# Licznik_minut.net
KiCad netlist of a schematic drawn in Altium Designer
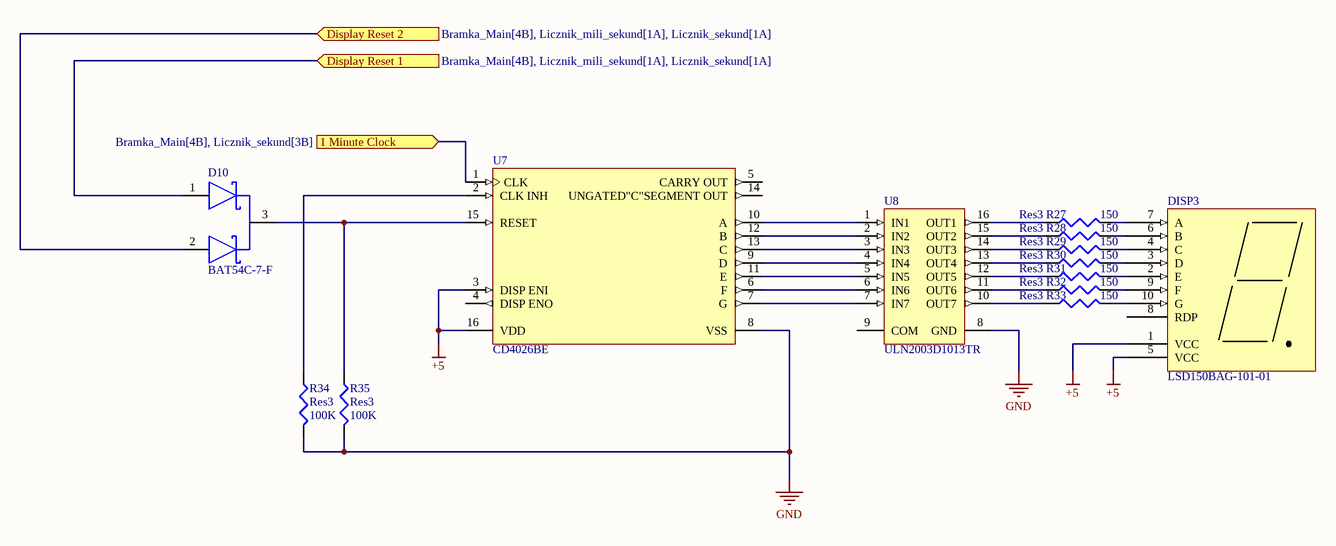
[diagram p0: Licznik_minut.SchDoc]

(export (version "E")
  (design (tool "Eeschema 10.0.6"))
  (components
    (comp (ref "D10")
      (value "BAT54C-7-F")
      (footprint "FP-SOT23-IPC_B")
      (description "DIODE ARRAY SCHOTTKY 30V SOT23-3")
      (libsource (lib "Altium Content Vault") (part "3eac2aa0c1ac86323ecc23460aa29c6"))
    )
    (comp (ref "DISP3")
      (value "LSD150BAG-101-01")
      (footprint "7 segment display")
      (description "7 segment display 1.5 inch")
      (libsource (lib "WUST") (part "LSD150BAG-101-01-Symbol-1"))
    )
    (comp (ref "R27")
      (value "Res3")
      (footprint "6-0805_M")
      (description "Resistor")
      (fields (field (name "ALTIUM_VALUE") "150") (field (name "PUBLISHER") "Altium Limited"))
      (libsource (lib "Miscellaneous Devices") (part "Res3"))
    )
    (comp (ref "R28")
      (value "Res3")
      (footprint "6-0805_M")
      (description "Resistor")
      (fields (field (name "ALTIUM_VALUE") "150") (field (name "PUBLISHER") "Altium Limited"))
      (libsource (lib "Miscellaneous Devices") (part "Res3"))
    )
    (comp (ref "R29")
      (value "Res3")
      (footprint "6-0805_M")
      (description "Resistor")
      (fields (field (name "ALTIUM_VALUE") "150") (field (name "PUBLISHER") "Altium Limited"))
      (libsource (lib "Miscellaneous Devices") (part "Res3"))
    )
    (comp (ref "R30")
      (value "Res3")
      (footprint "6-0805_M")
      (description "Resistor")
      (fields (field (name "ALTIUM_VALUE") "150") (field (name "PUBLISHER") "Altium Limited"))
      (libsource (lib "Miscellaneous Devices") (part "Res3"))
    )
    (comp (ref "R31")
      (value "Res3")
      (footprint "6-0805_M")
      (description "Resistor")
      (fields (field (name "ALTIUM_VALUE") "150") (field (name "PUBLISHER") "Altium Limited"))
      (libsource (lib "Miscellaneous Devices") (part "Res3"))
    )
    (comp (ref "R32")
      (value "Res3")
      (footprint "6-0805_M")
      (description "Resistor")
      (fields (field (name "ALTIUM_VALUE") "150") (field (name "PUBLISHER") "Altium Limited"))
      (libsource (lib "Miscellaneous Devices") (part "Res3"))
    )
    (comp (ref "R33")
      (value "Res3")
      (footprint "6-0805_M")
      (description "Resistor")
      (fields (field (name "ALTIUM_VALUE") "150") (field (name "PUBLISHER") "Altium Limited"))
      (libsource (lib "Miscellaneous Devices") (part "Res3"))
    )
    (comp (ref "R34")
      (value "Res3")
      (footprint "J1-0603")
      (description "Resistor")
      (fields (field (name "ALTIUM_VALUE") "100K") (field (name "PUBLISHER") "Altium Limited"))
      (libsource (lib "Miscellaneous Devices") (part "Res3"))
    )
    (comp (ref "R35")
      (value "Res3")
      (footprint "J1-0603")
      (description "Resistor")
      (fields (field (name "ALTIUM_VALUE") "100K") (field (name "PUBLISHER") "Altium Limited"))
      (libsource (lib "Miscellaneous Devices") (part "Res3"))
    )
    (comp (ref "U7")
      (value "CD4026BE")
      (footprint "N0016A")
      (fields
        (field (name "MANUFACTURER") "Texas Instruments")
        (field (name "GENERIC PART NUMBER") "CD4026B")
      )
      (libsource (lib "Altium Content Vault") (part "TI-CD4026B-16"))
    )
    (comp (ref "U8")
      (value "ULN2003D1013TR")
      (footprint "STM-SO-16_M")
      (fields (field (name "MANUFACTURER") "STMicroelectronics"))
      (libsource (lib "Altium Content Vault") (part "STM-ULN2003A-PDIP-16"))
    )
  )
  (nets
    (net (code "1") (name "+5") (class "Default")
      (node (ref "DISP3") (pin "1") (pinfunction "VCC_1") (pintype "power_in"))
      (node (ref "DISP3") (pin "5") (pinfunction "VCC_5") (pintype "power_in"))
      (node (ref "U7") (pin "16") (pinfunction "VDD_16") (pintype "power_in"))
      (node (ref "U7") (pin "3") (pinfunction "DISP_ENI_3") (pintype "input"))
    )
    (net (code "2") (name "/1 Minute Clock") (class "Default")
      (node (ref "U7") (pin "1") (pinfunction "CLK_1") (pintype "input"))
    )
    (net (code "3") (name "/Display Reset 1") (class "Default")
      (node (ref "D10") (pin "1") (pinfunction "1_ANODE_1") (pintype "passive"))
    )
    (net (code "4") (name "/Display Reset 2") (class "Default")
      (node (ref "D10") (pin "2") (pinfunction "2_ANODE_2") (pintype "passive"))
    )
    (net (code "5") (name "GND") (class "Default")
      (node (ref "R34") (pin "2") (pinfunction "2_2") (pintype "passive"))
      (node (ref "R35") (pin "2") (pinfunction "2_2") (pintype "passive"))
      (node (ref "U7") (pin "8") (pinfunction "VSS_8") (pintype "power_in"))
      (node (ref "U8") (pin "8") (pinfunction "GND_8") (pintype "power_in"))
    )
    (net (code "6") (name "Net-(D10-COMMON_CATHODE)") (class "Default")
      (node (ref "D10") (pin "3") (pinfunction "COMMON_CATHODE_3") (pintype "passive"))
      (node (ref "R35") (pin "1") (pinfunction "1_1") (pintype "passive"))
      (node (ref "U7") (pin "15") (pinfunction "RESET_15") (pintype "input"))
    )
    (net (code "7") (name "Net-(DISP3-A)") (class "Default")
      (node (ref "DISP3") (pin "7") (pinfunction "A_7") (pintype "input"))
      (node (ref "R27") (pin "2") (pinfunction "2_2") (pintype "passive"))
    )
    (net (code "8") (name "Net-(DISP3-B)") (class "Default")
      (node (ref "DISP3") (pin "6") (pinfunction "B_6") (pintype "input"))
      (node (ref "R28") (pin "2") (pinfunction "2_2") (pintype "passive"))
    )
    (net (code "9") (name "Net-(DISP3-C)") (class "Default")
      (node (ref "DISP3") (pin "4") (pinfunction "C_4") (pintype "input"))
      (node (ref "R29") (pin "2") (pinfunction "2_2") (pintype "passive"))
    )
    (net (code "10") (name "Net-(DISP3-D)") (class "Default")
      (node (ref "DISP3") (pin "3") (pinfunction "D_3") (pintype "input"))
      (node (ref "R30") (pin "2") (pinfunction "2_2") (pintype "passive"))
    )
    (net (code "11") (name "Net-(DISP3-E)") (class "Default")
      (node (ref "DISP3") (pin "2") (pinfunction "E_2") (pintype "input"))
      (node (ref "R31") (pin "2") (pinfunction "2_2") (pintype "passive"))
    )
    (net (code "12") (name "Net-(DISP3-F)") (class "Default")
      (node (ref "DISP3") (pin "9") (pinfunction "F_9") (pintype "input"))
      (node (ref "R32") (pin "2") (pinfunction "2_2") (pintype "passive"))
    )
    (net (code "13") (name "Net-(DISP3-G)") (class "Default")
      (node (ref "DISP3") (pin "10") (pinfunction "G_10") (pintype "input"))
      (node (ref "R33") (pin "2") (pinfunction "2_2") (pintype "passive"))
    )
    (net (code "14") (name "Net-(U7-A)") (class "Default")
      (node (ref "U7") (pin "10") (pinfunction "A_10") (pintype "output"))
      (node (ref "U8") (pin "1") (pinfunction "IN1_1") (pintype "input"))
    )
    (net (code "15") (name "Net-(U7-B)") (class "Default")
      (node (ref "U7") (pin "12") (pinfunction "B_12") (pintype "output"))
      (node (ref "U8") (pin "2") (pinfunction "IN2_2") (pintype "input"))
    )
    (net (code "16") (name "Net-(U7-C)") (class "Default")
      (node (ref "U7") (pin "13") (pinfunction "C_13") (pintype "output"))
      (node (ref "U8") (pin "3") (pinfunction "IN3_3") (pintype "input"))
    )
    (net (code "17") (name "Net-(U7-CLK_INH)") (class "Default")
      (node (ref "R34") (pin "1") (pinfunction "1_1") (pintype "passive"))
      (node (ref "U7") (pin "2") (pinfunction "CLK_INH_2") (pintype "input"))
    )
    (net (code "18") (name "Net-(U7-D)") (class "Default")
      (node (ref "U7") (pin "9") (pinfunction "D_9") (pintype "output"))
      (node (ref "U8") (pin "4") (pinfunction "IN4_4") (pintype "input"))
    )
    (net (code "19") (name "Net-(U7-E)") (class "Default")
      (node (ref "U7") (pin "11") (pinfunction "E_11") (pintype "output"))
      (node (ref "U8") (pin "5") (pinfunction "IN5_5") (pintype "input"))
    )
    (net (code "20") (name "Net-(U7-F)") (class "Default")
      (node (ref "U7") (pin "6") (pinfunction "F_6") (pintype "output"))
      (node (ref "U8") (pin "6") (pinfunction "IN6_6") (pintype "input"))
    )
    (net (code "21") (name "Net-(U7-G)") (class "Default")
      (node (ref "U7") (pin "7") (pinfunction "G_7") (pintype "output"))
      (node (ref "U8") (pin "7") (pinfunction "IN7_7") (pintype "input"))
    )
    (net (code "22") (name "Net-(U8-OUT1)") (class "Default")
      (node (ref "R27") (pin "1") (pinfunction "1_1") (pintype "passive"))
      (node (ref "U8") (pin "16") (pinfunction "OUT1_16") (pintype "output"))
    )
    (net (code "23") (name "Net-(U8-OUT2)") (class "Default")
      (node (ref "R28") (pin "1") (pinfunction "1_1") (pintype "passive"))
      (node (ref "U8") (pin "15") (pinfunction "OUT2_15") (pintype "output"))
    )
    (net (code "24") (name "Net-(U8-OUT3)") (class "Default")
      (node (ref "R29") (pin "1") (pinfunction "1_1") (pintype "passive"))
      (node (ref "U8") (pin "14") (pinfunction "OUT3_14") (pintype "output"))
    )
    (net (code "25") (name "Net-(U8-OUT4)") (class "Default")
      (node (ref "R30") (pin "1") (pinfunction "1_1") (pintype "passive"))
      (node (ref "U8") (pin "13") (pinfunction "OUT4_13") (pintype "output"))
    )
    (net (code "26") (name "Net-(U8-OUT5)") (class "Default")
      (node (ref "R31") (pin "1") (pinfunction "1_1") (pintype "passive"))
      (node (ref "U8") (pin "12") (pinfunction "OUT5_12") (pintype "output"))
    )
    (net (code "27") (name "Net-(U8-OUT6)") (class "Default")
      (node (ref "R32") (pin "1") (pinfunction "1_1") (pintype "passive"))
      (node (ref "U8") (pin "11") (pinfunction "OUT6_11") (pintype "output"))
    )
    (net (code "28") (name "Net-(U8-OUT7)") (class "Default")
      (node (ref "R33") (pin "1") (pinfunction "1_1") (pintype "passive"))
      (node (ref "U8") (pin "10") (pinfunction "OUT7_10") (pintype "output"))
    )
    (net (code "29") (name "unconnected-(DISP3-RDP-Pad8)") (class "Default")
      (node (ref "DISP3") (pin "8") (pinfunction "RDP_8") (pintype "passive"))
    )
    (net (code "30") (name "unconnected-(U7-CARRY_OUT-Pad5)") (class "Default")
      (node (ref "U7") (pin "5") (pinfunction "CARRY_OUT_5") (pintype "output"))
    )
    (net (code "31") (name "unconnected-(U7-DISP_ENO-Pad4)") (class "Default")
      (node (ref "U7") (pin "4") (pinfunction "DISP_ENO_4") (pintype "output"))
    )
    (net (code "32") (name "unconnected-(U7-UNGATED\"C\"SEGMENT_OUT-Pad14)") (class "Default")
      (node (ref "U7") (pin "14") (pinfunction "UNGATED\"C\"SEGMENT_OUT_14") (pintype "output"))
    )
    (net (code "33") (name "unconnected-(U8-COM-Pad9)") (class "Default")
      (node (ref "U8") (pin "9") (pinfunction "COM_9") (pintype "passive"))
    )
  )
)
